# MetalDectectorFinaltext1.net
KiCad netlist of a schematic drawn in EAGLE
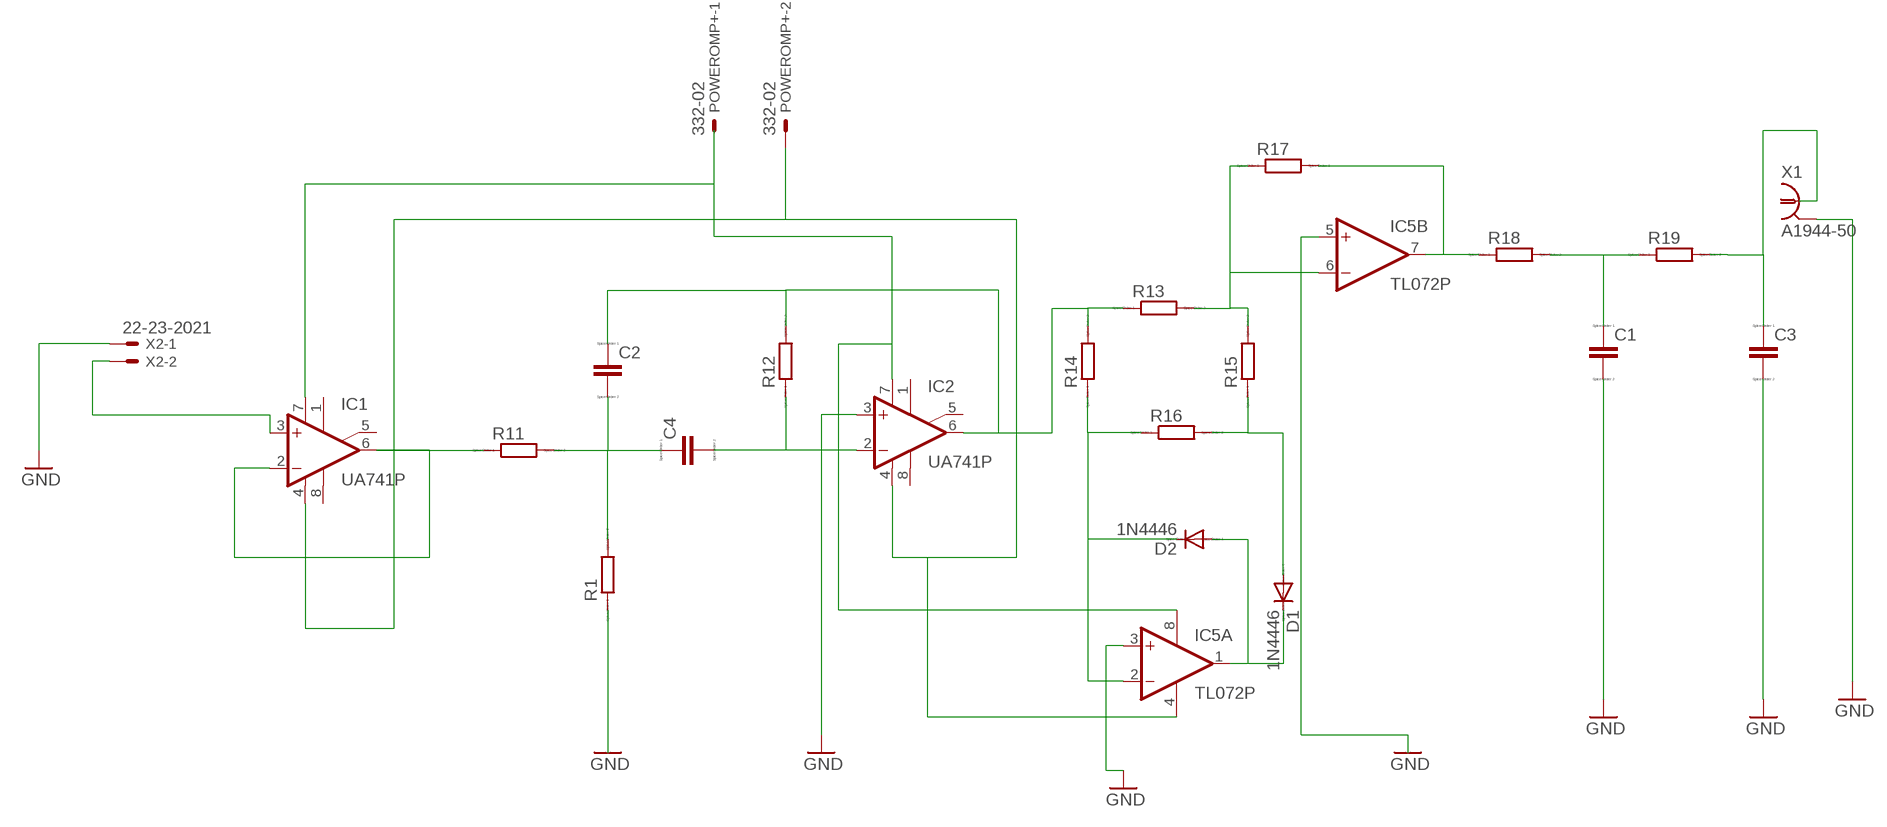
[diagram p0: schematic, sheet 1]

(export (version "E")
  (design (tool "Eeschema 10.0.6"))
  (components
    (comp (ref "C1")
      (value "C-EU025-025X050")
      (footprint "eagle-import:C025-025X050")
      (libsource (lib "eagle-import") (part "C-EU025-025X050"))
    )
    (comp (ref "C2")
      (value "C-EU025-025X050")
      (footprint "eagle-import:C025-025X050")
      (libsource (lib "eagle-import") (part "C-EU025-025X050"))
    )
    (comp (ref "C3")
      (value "C-EU025-025X050")
      (footprint "eagle-import:C025-025X050")
      (libsource (lib "eagle-import") (part "C-EU025-025X050"))
    )
    (comp (ref "C4")
      (value "C-EU025-025X050")
      (footprint "eagle-import:C025-025X050")
      (libsource (lib "eagle-import") (part "C-EU025-025X050"))
    )
    (comp (ref "D1")
      (value "1N4446")
      (footprint "eagle-import:DO35-10")
      (libsource (lib "eagle-import") (part "1N4446"))
    )
    (comp (ref "D2")
      (value "1N4446")
      (footprint "eagle-import:DO35-10")
      (libsource (lib "eagle-import") (part "1N4446"))
    )
    (comp (ref "IC1")
      (value "UA741P")
      (footprint "eagle-import:DIL08")
      (libsource (lib "eagle-import") (part "741PUA"))
    )
    (comp (ref "IC2")
      (value "UA741P")
      (footprint "eagle-import:DIL08")
      (libsource (lib "eagle-import") (part "741PUA"))
    )
    (comp (ref "IC5")
      (value "TL072P")
      (footprint "eagle-import:DIL08")
      (libsource (lib "eagle-import") (part "TL072P"))
    )
    (comp (ref "POWEROMP+")
      (value "332-02")
      (footprint "eagle-import:332-02")
      (libsource (lib "eagle-import") (part "332-02"))
    )
    (comp (ref "R1")
      (value "R-EU_0204_7")
      (footprint "eagle-import:0204_7")
      (libsource (lib "eagle-import") (part "R-EU_0204_7"))
    )
    (comp (ref "R11")
      (value "R-EU_0204_7")
      (footprint "eagle-import:0204_7")
      (libsource (lib "eagle-import") (part "R-EU_0204_7"))
    )
    (comp (ref "R12")
      (value "R-EU_0204_7")
      (footprint "eagle-import:0204_7")
      (libsource (lib "eagle-import") (part "R-EU_0204_7"))
    )
    (comp (ref "R13")
      (value "R-EU_0204_7")
      (footprint "eagle-import:0204_7")
      (libsource (lib "eagle-import") (part "R-EU_0204_7"))
    )
    (comp (ref "R14")
      (value "R-EU_0204_7")
      (footprint "eagle-import:0204_7")
      (libsource (lib "eagle-import") (part "R-EU_0204_7"))
    )
    (comp (ref "R15")
      (value "R-EU_0204_7")
      (footprint "eagle-import:0204_7")
      (libsource (lib "eagle-import") (part "R-EU_0204_7"))
    )
    (comp (ref "R16")
      (value "R-EU_0204_7")
      (footprint "eagle-import:0204_7")
      (libsource (lib "eagle-import") (part "R-EU_0204_7"))
    )
    (comp (ref "R17")
      (value "R-EU_0204_7")
      (footprint "eagle-import:0204_7")
      (libsource (lib "eagle-import") (part "R-EU_0204_7"))
    )
    (comp (ref "R18")
      (value "R-EU_0204_7")
      (footprint "eagle-import:0204_7")
      (libsource (lib "eagle-import") (part "R-EU_0204_7"))
    )
    (comp (ref "R19")
      (value "R-EU_0204_7")
      (footprint "eagle-import:0204_7")
      (libsource (lib "eagle-import") (part "R-EU_0204_7"))
    )
    (comp (ref "X1")
      (value "A1944-50")
      (footprint "eagle-import:A1944")
      (libsource (lib "eagle-import") (part "A1944-50"))
    )
    (comp (ref "X2")
      (value "22-23-2021")
      (footprint "eagle-import:22-23-2021")
      (fields (field (name "MF") "MOLEX"))
      (libsource (lib "eagle-import") (part "22-23-2021"))
    )
  )
  (nets
    (net (code "1") (name "GND") (class "Default")
      (node (ref "C1") (pin "2") (pinfunction "2_2") (pintype "passive"))
      (node (ref "C3") (pin "2") (pinfunction "2_2") (pintype "passive"))
      (node (ref "IC2") (pin "3") (pinfunction "+IN_3") (pintype "input"))
      (node (ref "IC5") (pin "3") (pinfunction "+IN_3") (pintype "input"))
      (node (ref "IC5") (pin "5") (pinfunction "+IN_5") (pintype "input"))
      (node (ref "X1") (pin "2") (pinfunction "2_2") (pintype "passive"))
      (node (ref "X1") (pin "3") (pinfunction "2_3") (pintype "passive"))
      (node (ref "X1") (pin "4") (pinfunction "2_4") (pintype "passive"))
      (node (ref "X1") (pin "5") (pinfunction "2_5") (pintype "passive"))
      (node (ref "X2") (pin "1") (pinfunction "S_1") (pintype "passive"))
    )
    (net (code "2") (name "Net-(C1-Pad1)") (class "Default")
      (node (ref "C1") (pin "1") (pinfunction "1_1") (pintype "passive"))
      (node (ref "R18") (pin "2") (pinfunction "2_2") (pintype "passive"))
      (node (ref "R19") (pin "1") (pinfunction "1_1") (pintype "passive"))
    )
    (net (code "3") (name "Net-(C2-Pad2)") (class "Default")
      (node (ref "C2") (pin "2") (pinfunction "2_2") (pintype "passive"))
      (node (ref "C4") (pin "1") (pinfunction "1_1") (pintype "passive"))
      (node (ref "R1") (pin "2") (pinfunction "2_2") (pintype "passive"))
      (node (ref "R11") (pin "2") (pinfunction "2_2") (pintype "passive"))
    )
    (net (code "4") (name "Net-(C3-Pad1)") (class "Default")
      (node (ref "C3") (pin "1") (pinfunction "1_1") (pintype "passive"))
      (node (ref "R19") (pin "2") (pinfunction "2_2") (pintype "passive"))
      (node (ref "X1") (pin "1") (pinfunction "1_1") (pintype "passive"))
    )
    (net (code "5") (name "Net-(D1-PadA)") (class "Default")
      (node (ref "D1") (pin "A") (pinfunction "A_A") (pintype "passive"))
      (node (ref "R15") (pin "1") (pinfunction "1_1") (pintype "passive"))
      (node (ref "R16") (pin "2") (pinfunction "2_2") (pintype "passive"))
    )
    (net (code "6") (name "Net-(IC1-+IN)") (class "Default")
      (node (ref "IC1") (pin "3") (pinfunction "+IN_3") (pintype "input"))
      (node (ref "X2") (pin "2") (pinfunction "S_2") (pintype "passive"))
    )
    (net (code "7") (name "Net-(IC1--IN)") (class "Default")
      (node (ref "IC1") (pin "2") (pinfunction "-IN_2") (pintype "input"))
      (node (ref "IC1") (pin "6") (pinfunction "OUT_6") (pintype "output"))
      (node (ref "R11") (pin "1") (pinfunction "1_1") (pintype "passive"))
    )
    (net (code "8") (name "Net-(IC1-V+)") (class "Default")
      (node (ref "IC1") (pin "7") (pinfunction "V+_7") (pintype "power_in"))
      (node (ref "IC2") (pin "7") (pinfunction "V+_7") (pintype "power_in"))
      (node (ref "IC5") (pin "8") (pinfunction "V+_8") (pintype "power_in"))
      (node (ref "POWEROMP+") (pin "1") (pinfunction "S_1") (pintype "passive"))
    )
    (net (code "9") (name "Net-(IC1-V-)") (class "Default")
      (node (ref "IC1") (pin "4") (pinfunction "V-_4") (pintype "power_in"))
      (node (ref "IC2") (pin "4") (pinfunction "V-_4") (pintype "power_in"))
      (node (ref "IC5") (pin "4") (pinfunction "V-_4") (pintype "power_in"))
      (node (ref "POWEROMP+") (pin "2") (pinfunction "S_2") (pintype "passive"))
    )
    (net (code "10") (name "Net-(IC2--IN)") (class "Default")
      (node (ref "C4") (pin "2") (pinfunction "2_2") (pintype "passive"))
      (node (ref "IC2") (pin "2") (pinfunction "-IN_2") (pintype "input"))
      (node (ref "R12") (pin "1") (pinfunction "1_1") (pintype "passive"))
    )
    (net (code "11") (name "Net-(IC2-OUT)") (class "Default")
      (node (ref "C2") (pin "1") (pinfunction "1_1") (pintype "passive"))
      (node (ref "IC2") (pin "6") (pinfunction "OUT_6") (pintype "output"))
      (node (ref "R12") (pin "2") (pinfunction "2_2") (pintype "passive"))
      (node (ref "R13") (pin "1") (pinfunction "1_1") (pintype "passive"))
      (node (ref "R14") (pin "2") (pinfunction "2_2") (pintype "passive"))
    )
    (net (code "12") (name "Net-(IC5A--IN)") (class "Default")
      (node (ref "D2") (pin "C") (pinfunction "C_C") (pintype "passive"))
      (node (ref "IC5") (pin "2") (pinfunction "-IN_2") (pintype "input"))
      (node (ref "R14") (pin "1") (pinfunction "1_1") (pintype "passive"))
      (node (ref "R16") (pin "1") (pinfunction "1_1") (pintype "passive"))
    )
    (net (code "13") (name "Net-(IC5A-OUT)") (class "Default")
      (node (ref "D1") (pin "C") (pinfunction "C_C") (pintype "passive"))
      (node (ref "D2") (pin "A") (pinfunction "A_A") (pintype "passive"))
      (node (ref "IC5") (pin "1") (pinfunction "OUT_1") (pintype "output"))
    )
    (net (code "14") (name "Net-(IC5B--IN)") (class "Default")
      (node (ref "IC5") (pin "6") (pinfunction "-IN_6") (pintype "input"))
      (node (ref "R13") (pin "2") (pinfunction "2_2") (pintype "passive"))
      (node (ref "R15") (pin "2") (pinfunction "2_2") (pintype "passive"))
      (node (ref "R17") (pin "1") (pinfunction "1_1") (pintype "passive"))
    )
    (net (code "15") (name "Net-(IC5B-OUT)") (class "Default")
      (node (ref "IC5") (pin "7") (pinfunction "OUT_7") (pintype "output"))
      (node (ref "R17") (pin "2") (pinfunction "2_2") (pintype "passive"))
      (node (ref "R18") (pin "1") (pinfunction "1_1") (pintype "passive"))
    )
    (net (code "16") (name "unconnected-(IC1-ON1-Pad1)") (class "Default")
      (node (ref "IC1") (pin "1") (pinfunction "ON1_1") (pintype "passive"))
    )
    (net (code "17") (name "unconnected-(IC1-ON2-Pad5)") (class "Default")
      (node (ref "IC1") (pin "5") (pinfunction "ON2_5") (pintype "passive"))
    )
    (net (code "18") (name "unconnected-(IC1-OPT-Pad8)") (class "Default")
      (node (ref "IC1") (pin "8") (pinfunction "OPT_8") (pintype "passive"))
    )
    (net (code "19") (name "unconnected-(IC2-ON1-Pad1)") (class "Default")
      (node (ref "IC2") (pin "1") (pinfunction "ON1_1") (pintype "passive"))
    )
    (net (code "20") (name "unconnected-(IC2-ON2-Pad5)") (class "Default")
      (node (ref "IC2") (pin "5") (pinfunction "ON2_5") (pintype "passive"))
    )
    (net (code "21") (name "unconnected-(IC2-OPT-Pad8)") (class "Default")
      (node (ref "IC2") (pin "8") (pinfunction "OPT_8") (pintype "passive"))
    )
    (net (code "22") (name "unconnected-(R1-Pad1)") (class "Default")
      (node (ref "R1") (pin "1") (pinfunction "1_1") (pintype "passive"))
    )
  )
)
